# Communications.net
KiCad netlist of a schematic drawn in Altium Designer
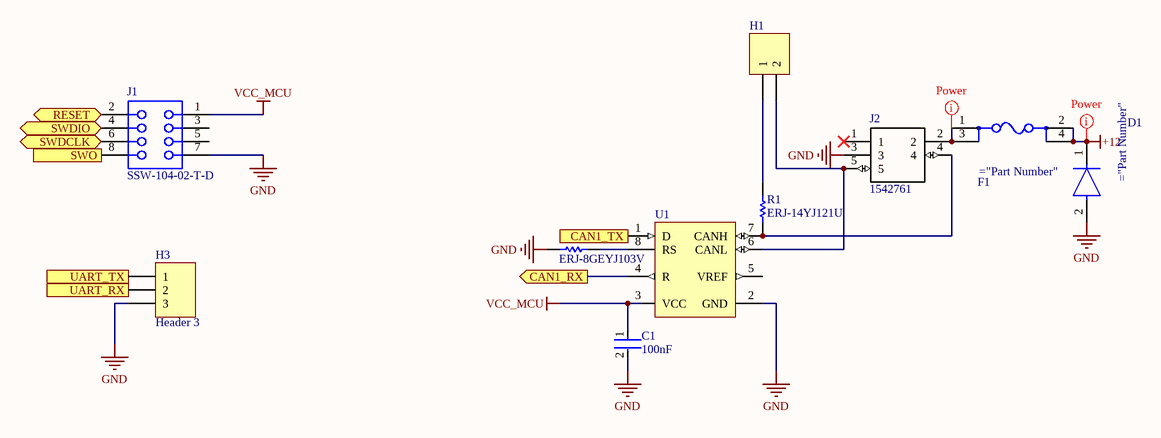
[diagram p0: Communications.SchDoc]

(export (version "E")
  (design (tool "Eeschema 10.0.6"))
  (components
    (comp (ref "C1")
      (value "100nF")
      (footprint "Kemet_C0603_IPC_A")
      (description "CAP CER 0.1UF 100NF 50V X7R 0603 C0603C104K5RACTU")
      (libsource (lib "UNK_Kemet_C0603C104K5RACTU_eec") (part "C0603C104K5RACTU"))
    )
    (comp (ref "D1")
      (value "S1J-13-F")
      (footprint "Diodes_SMA_0")
      (libsource (lib "Diode_Diodes_S1J-13-F_eec") (part "S1J-13-F"))
    )
    (comp (ref "F1")
      (value "3557-2")
      (footprint "Keystone_3557-2_0")
      (libsource (lib "Fuse_Keystone_3557-2_eec") (part "3557-2"))
    )
    (comp (ref "H1")
      (value "Header 0")
      (footprint "HDR1X2")
      (description "Header, 2-Pin")
      (fields (field (name "PUBLISHER") "Altium Limited"))
      (libsource (lib "Miscellaneous Connectors") (part "Header 2"))
    )
    (comp (ref "H3")
      (value "Header 3")
      (footprint "HDR1X3")
      (description "Header, 3-Pin")
      (fields (field (name "PUBLISHER") "Altium Limited"))
      (libsource (lib "Miscellaneous Connectors") (part "Header 3"))
    )
    (comp (ref "J1")
      (value "SSW-104-02-T-D")
      (footprint "SMTC-SSW-104-02-X-D")
      (description "SQ Post Socket, Through-hole, Vertical, -55 to 105 degC, 2.54mm Pitch, 8-Pin, Female, RoHS")
      (fields (field (name "MANUFACTURER") "Samtec"))
      (libsource (lib "Altium Content Vault") (part "SMTC-SSW-104-X-X-D"))
    )
    (comp (ref "J2")
      (value "1542761")
      (footprint "SamacSys:1542761")
      (description "Connector")
      (fields (field (name "MOUSER PART NUMBER") "651-1542761") (field (name "RS PART NUMBER") "8025583"))
      (libsource (lib "*") (part "1542761"))
    )
    (comp (ref "R1")
      (value "ERJ-14YJ121U")
      (footprint "RESC3225X70X50ML20T20")
      (description "120Ohm")
      (fields (field (name "MANUFACTURER") "Panasonic"))
      (libsource (lib "Altium Content Vault") (part "RES"))
    )
    (comp (ref "R2")
      (value "ERJ-8GEYJ103V")
      (footprint "RESC3216X70X50NL05T20")
      (description "10k")
      (fields (field (name "MANUFACTURER") "Panasonic"))
      (libsource (lib "Altium Content Vault") (part "RES"))
    )
    (comp (ref "U1")
      (value "SN65HVD230D")
      (footprint "D0008A_M")
      (description "CAN Bus Transceiver, 3.3 V, -40 to 85 degC, 8-Pin SOIC (D), Green (RoHS & no Sb/Br), Tube")
      (fields (field (name "GENERIC PART NUMBER") "SN65HVD230"))
      (libsource (lib "Altium Content Vault") (part "TI-SN65HVD230D-SOIC_D-8"))
    )
  )
  (nets
    (net (code "1") (name "+12") (class "Default")
      (node (ref "D1") (pin "1") (pinfunction "C_1") (pintype "passive"))
      (node (ref "F1") (pin "2") (pinfunction "2_2") (pintype "passive"))
      (node (ref "F1") (pin "4") (pinfunction "4_4") (pintype "passive"))
    )
    (net (code "2") (name "/CAN1_RX") (class "Default")
      (node (ref "U1") (pin "4") (pinfunction "R_4") (pintype "output"))
    )
    (net (code "3") (name "/CAN1_TX") (class "Default")
      (node (ref "U1") (pin "1") (pinfunction "D_1") (pintype "input"))
    )
    (net (code "4") (name "/RESET") (class "Default")
      (node (ref "J1") (pin "2") (pinfunction "2_2") (pintype "passive"))
    )
    (net (code "5") (name "/SWDCLK") (class "Default")
      (node (ref "J1") (pin "6") (pinfunction "6_6") (pintype "passive"))
    )
    (net (code "6") (name "/SWDIO") (class "Default")
      (node (ref "J1") (pin "4") (pinfunction "4_4") (pintype "passive"))
    )
    (net (code "7") (name "/SWO") (class "Default")
      (node (ref "J1") (pin "8") (pinfunction "8_8") (pintype "passive"))
    )
    (net (code "8") (name "/UART_RX") (class "Default")
      (node (ref "H3") (pin "2") (pinfunction "2_2") (pintype "passive"))
    )
    (net (code "9") (name "/UART_TX") (class "Default")
      (node (ref "H3") (pin "1") (pinfunction "1_1") (pintype "passive"))
    )
    (net (code "10") (name "GND") (class "Default")
      (node (ref "C1") (pin "2") (pinfunction "2_2") (pintype "passive"))
      (node (ref "D1") (pin "2") (pinfunction "A_2") (pintype "passive"))
      (node (ref "H3") (pin "3") (pinfunction "3_3") (pintype "passive"))
      (node (ref "J1") (pin "7") (pinfunction "7_7") (pintype "passive"))
      (node (ref "J2") (pin "3") (pinfunction "3_3") (pintype "power_in"))
      (node (ref "R2") (pin "2") (pinfunction "2_2") (pintype "passive"))
      (node (ref "U1") (pin "2") (pinfunction "GND_2") (pintype "power_in"))
    )
    (net (code "11") (name "Net-(F1-Pad1)") (class "Default")
      (node (ref "F1") (pin "1") (pinfunction "1_1") (pintype "passive"))
      (node (ref "F1") (pin "3") (pinfunction "3_3") (pintype "passive"))
      (node (ref "J2") (pin "2") (pinfunction "2_2") (pintype "power_in"))
    )
    (net (code "12") (name "Net-(H1-Pad1)") (class "Default")
      (node (ref "H1") (pin "1") (pinfunction "1_1") (pintype "passive"))
      (node (ref "R1") (pin "2") (pinfunction "2_2") (pintype "passive"))
    )
    (net (code "13") (name "Net-(U1-CANH)") (class "Default")
      (node (ref "J2") (pin "4") (pinfunction "4_4") (pintype "bidirectional"))
      (node (ref "R1") (pin "1") (pinfunction "1_1") (pintype "passive"))
      (node (ref "U1") (pin "7") (pinfunction "CANH_7") (pintype "bidirectional"))
    )
    (net (code "14") (name "Net-(U1-CANL)") (class "Default")
      (node (ref "H1") (pin "2") (pinfunction "2_2") (pintype "passive"))
      (node (ref "J2") (pin "5") (pinfunction "5_5") (pintype "bidirectional"))
      (node (ref "U1") (pin "6") (pinfunction "CANL_6") (pintype "bidirectional"))
    )
    (net (code "15") (name "Net-(U1-RS)") (class "Default")
      (node (ref "R2") (pin "1") (pinfunction "1_1") (pintype "passive"))
      (node (ref "U1") (pin "8") (pinfunction "RS_8") (pintype "passive"))
    )
    (net (code "16") (name "VCC_MCU") (class "Default")
      (node (ref "C1") (pin "1") (pinfunction "1_1") (pintype "passive"))
      (node (ref "J1") (pin "1") (pinfunction "1_1") (pintype "passive"))
      (node (ref "U1") (pin "3") (pinfunction "VCC_3") (pintype "power_in"))
    )
    (net (code "17") (name "unconnected-(J1-Pad3)") (class "Default")
      (node (ref "J1") (pin "3") (pinfunction "3_3") (pintype "passive"))
    )
    (net (code "18") (name "unconnected-(J1-Pad5)") (class "Default")
      (node (ref "J1") (pin "5") (pinfunction "5_5") (pintype "passive"))
    )
    (net (code "19") (name "unconnected-(J2-Pad1)") (class "Default")
      (node (ref "J2") (pin "1") (pinfunction "1_1") (pintype "passive+no_connect"))
    )
    (net (code "20") (name "unconnected-(U1-VREF-Pad5)") (class "Default")
      (node (ref "U1") (pin "5") (pinfunction "VREF_5") (pintype "output"))
    )
  )
)
